# connectors-interface.net
KiCad netlist of a schematic drawn in Altium Designer
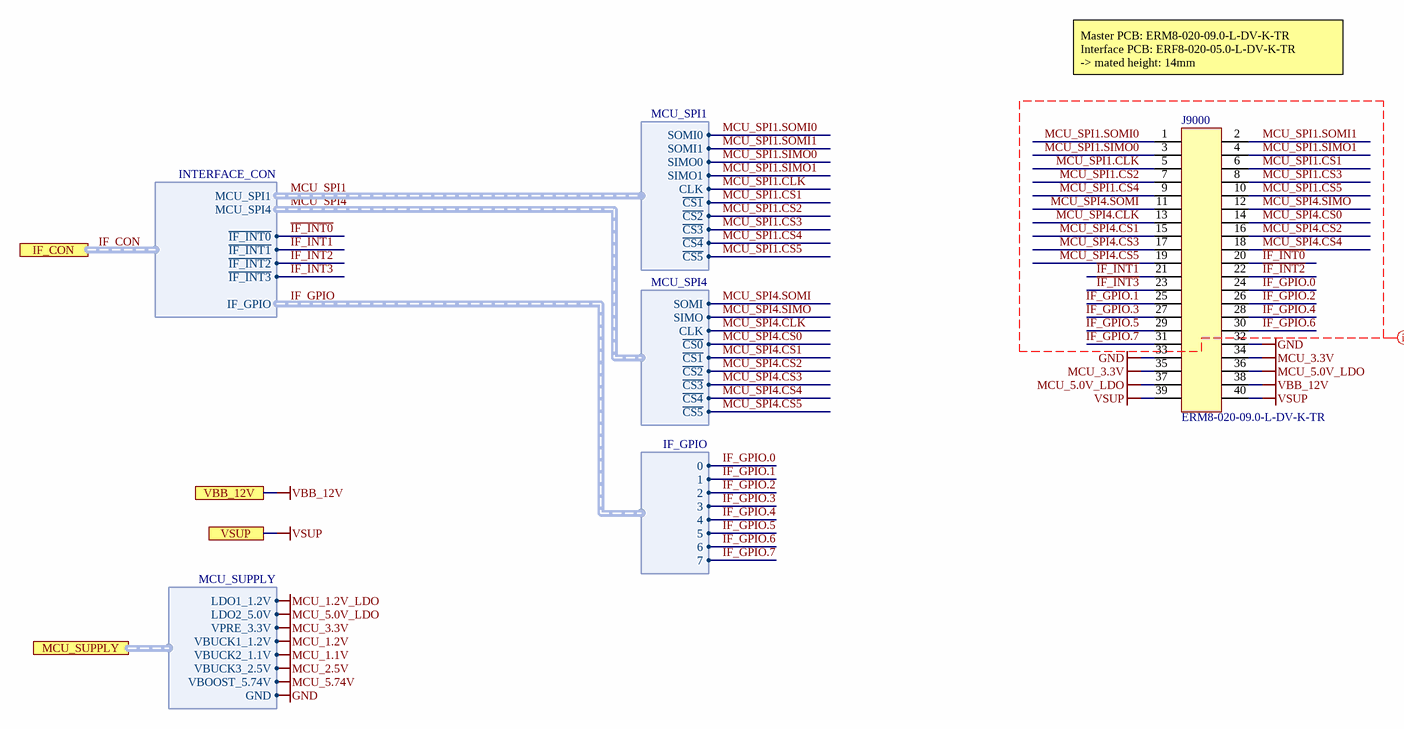
[diagram p0: connectors-interface.SchDoc]

(export (version "E")
  (design (tool "Eeschema 10.0.6"))
  (components
    (comp (ref "J9000")
      (value "ERM8-020-09.0-L-DV-K-TR")
      (footprint "SAMTEC_ERM8-020-09.0-L-DV-K")
      (description "Edge Rate rugged high-speed connector strips")
      (fields
        (field (name "PART NUMBER") "SAMTEC_ERM8-020-09.0-L-DV-K-TR")
        (field (name "MANUFACTURER") "Samtec")
      )
      (libsource (lib "OE750") (part "SAMTEC_ERM8-020-09.0-L-DV-K"))
    )
  )
  (nets
    (net (code "6") (name "/IF_GPIO.0") (class "Default") (node (ref "J9000") (pin "24") (pintype "passive")))
    (net (code "7") (name "/IF_GPIO.1") (class "Default") (node (ref "J9000") (pin "25") (pintype "passive")))
    (net (code "8") (name "/IF_GPIO.2") (class "Default") (node (ref "J9000") (pin "26") (pintype "passive")))
    (net (code "9") (name "/IF_GPIO.3") (class "Default") (node (ref "J9000") (pin "27") (pintype "passive")))
    (net (code "10") (name "/IF_GPIO.4") (class "Default")
      (node (ref "J9000") (pin "28") (pintype "passive"))
    )
    (net (code "11") (name "/IF_GPIO.5") (class "Default")
      (node (ref "J9000") (pin "29") (pintype "passive"))
    )
    (net (code "12") (name "/IF_GPIO.6") (class "Default")
      (node (ref "J9000") (pin "30") (pintype "passive"))
    )
    (net (code "13") (name "/IF_GPIO.7") (class "Default")
      (node (ref "J9000") (pin "31") (pintype "passive"))
    )
    (net (code "15") (name "/IF_INT0") (class "Default") (node (ref "J9000") (pin "20") (pintype "passive")))
    (net (code "16") (name "/IF_INT1") (class "Default") (node (ref "J9000") (pin "21") (pintype "passive")))
    (net (code "17") (name "/IF_INT2") (class "Default") (node (ref "J9000") (pin "22") (pintype "passive")))
    (net (code "18") (name "/IF_INT3") (class "Default") (node (ref "J9000") (pin "23") (pintype "passive")))
    (net (code "19") (name "/MCU_SPI1.CLK") (class "Default")
      (node (ref "J9000") (pin "5") (pintype "passive"))
    )
    (net (code "20") (name "/MCU_SPI1.CS1") (class "Default")
      (node (ref "J9000") (pin "6") (pintype "passive"))
    )
    (net (code "21") (name "/MCU_SPI1.CS2") (class "Default")
      (node (ref "J9000") (pin "7") (pintype "passive"))
    )
    (net (code "22") (name "/MCU_SPI1.CS3") (class "Default")
      (node (ref "J9000") (pin "8") (pintype "passive"))
    )
    (net (code "23") (name "/MCU_SPI1.CS4") (class "Default")
      (node (ref "J9000") (pin "9") (pintype "passive"))
    )
    (net (code "24") (name "/MCU_SPI1.CS5") (class "Default")
      (node (ref "J9000") (pin "10") (pintype "passive"))
    )
    (net (code "25") (name "/MCU_SPI1.SIMO0") (class "Default")
      (node (ref "J9000") (pin "3") (pintype "passive"))
    )
    (net (code "26") (name "/MCU_SPI1.SIMO1") (class "Default")
      (node (ref "J9000") (pin "4") (pintype "passive"))
    )
    (net (code "27") (name "/MCU_SPI1.SOMI0") (class "Default")
      (node (ref "J9000") (pin "1") (pintype "passive"))
    )
    (net (code "28") (name "/MCU_SPI1.SOMI1") (class "Default")
      (node (ref "J9000") (pin "2") (pintype "passive"))
    )
    (net (code "30") (name "/MCU_SPI4.CLK") (class "Default")
      (node (ref "J9000") (pin "13") (pintype "passive"))
    )
    (net (code "31") (name "/MCU_SPI4.CS0") (class "Default")
      (node (ref "J9000") (pin "14") (pintype "passive"))
    )
    (net (code "32") (name "/MCU_SPI4.CS1") (class "Default")
      (node (ref "J9000") (pin "15") (pintype "passive"))
    )
    (net (code "33") (name "/MCU_SPI4.CS2") (class "Default")
      (node (ref "J9000") (pin "16") (pintype "passive"))
    )
    (net (code "34") (name "/MCU_SPI4.CS3") (class "Default")
      (node (ref "J9000") (pin "17") (pintype "passive"))
    )
    (net (code "35") (name "/MCU_SPI4.CS4") (class "Default")
      (node (ref "J9000") (pin "18") (pintype "passive"))
    )
    (net (code "36") (name "/MCU_SPI4.CS5") (class "Default")
      (node (ref "J9000") (pin "19") (pintype "passive"))
    )
    (net (code "37") (name "/MCU_SPI4.SIMO") (class "Default")
      (node (ref "J9000") (pin "12") (pintype "passive"))
    )
    (net (code "38") (name "/MCU_SPI4.SOMI") (class "Default")
      (node (ref "J9000") (pin "11") (pintype "passive"))
    )
    (net (code "42") (name "GND") (class "Default")
      (node (ref "J9000") (pin "32") (pintype "passive"))
      (node (ref "J9000") (pin "33") (pintype "passive"))
    )
    (net (code "47") (name "MCU_3.3V") (class "Default")
      (node (ref "J9000") (pin "34") (pintype "passive"))
      (node (ref "J9000") (pin "35") (pintype "passive"))
    )
    (net (code "48") (name "MCU_5.0V_LDO") (class "Default")
      (node (ref "J9000") (pin "36") (pintype "passive"))
      (node (ref "J9000") (pin "37") (pintype "passive"))
    )
    (net (code "50") (name "VBB_12V") (class "Default") (node (ref "J9000") (pin "38") (pintype "passive")))
    (net (code "51") (name "VSUP") (class "Default")
      (node (ref "J9000") (pin "39") (pintype "passive"))
      (node (ref "J9000") (pin "40") (pintype "passive"))
    )
  )
)
